# TIDA01398_MCU.net
KiCad netlist of a schematic drawn in Altium Designer
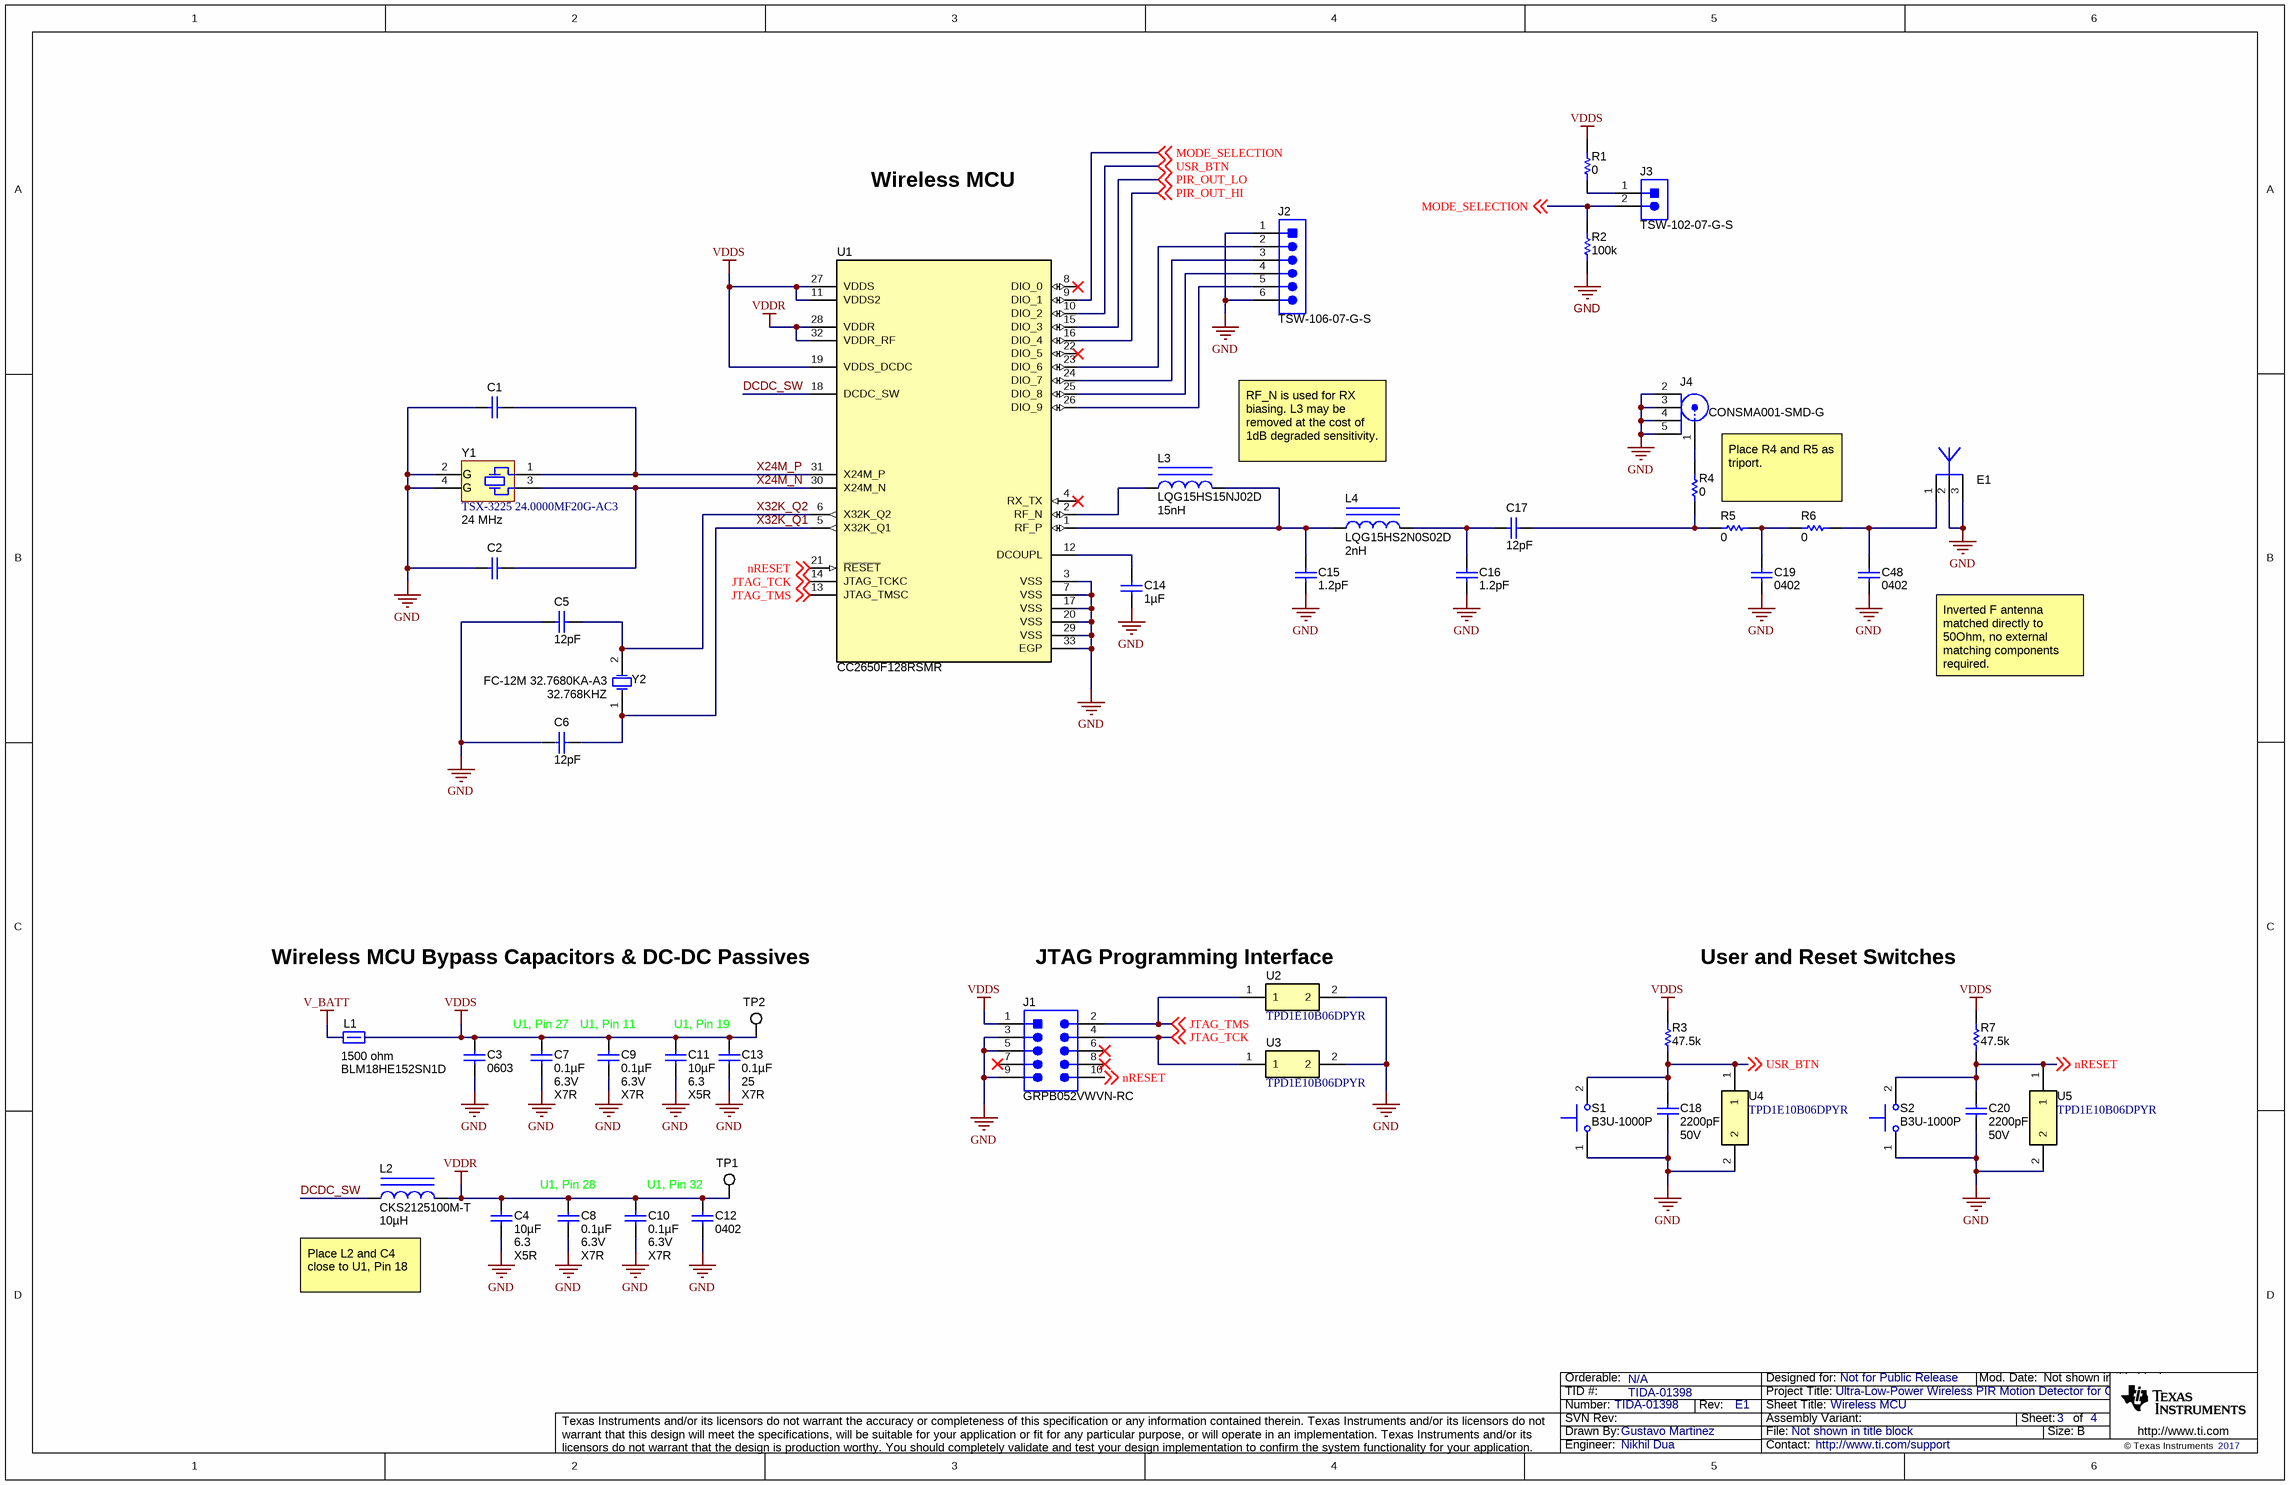
[diagram p0: TIDA01398_MCU.SchDoc]

(export (version "E")
  (design (tool "Eeschema 10.0.6"))
  (components
    (comp (ref "C1")
      (value "GRM1555C1E120JA01D")
      (footprint "0402")
      (description "CAP, CERM, 12 pF, 25 V, +/- 5%, C0G/NP0, 0402")
      (fields (field (name "MANUFACTURER") "MuRata") (field (name "PUBLISHER") "Texas Instruments"))
      (libsource (lib "Capacitor_Ceramic") (part "GRM1555C1E120JA01D"))
    )
    (comp (ref "C2")
      (value "GRM1555C1E120JA01D")
      (footprint "0402")
      (description "CAP, CERM, 12 pF, 25 V, +/- 5%, C0G/NP0, 0402")
      (fields (field (name "MANUFACTURER") "MuRata") (field (name "PUBLISHER") "Texas Instruments"))
      (libsource (lib "Capacitor_Ceramic") (part "GRM1555C1E120JA01D"))
    )
    (comp (ref "C3")
      (value "Used in BOM report")
      (footprint "0603")
      (description "CAP, CERM, xxxF, xxV, [TempCo], xx%, [PackageReference]")
      (fields (field (name "PACKAGEREFERENCE") "0603") (field (name "PUBLISHER") "Texas Instruments"))
      (libsource (lib "MiscParts") (part "Capacitor"))
    )
    (comp (ref "C4")
      (value "GRM188R60J106ME47D")
      (footprint "0603")
      (description "CAP, CERM, 10 µF, 6.3 V, +/- 20%, X5R, 0603")
      (fields
        (field (name "VALUEDISPLAYED") "10µF")
        (field (name "MANUFACTURER") "MuRata")
        (field (name "VDC_V") "6.3")
        (field (name "TEMPCO") "X5R")
        (field (name "PUBLISHER") "Texas Instruments")
      )
      (libsource (lib "Capacitor_Ceramic") (part "GRM188R60J106ME47D"))
    )
    (comp (ref "C5")
      (value "GRM1555C1E120JA01D")
      (footprint "0402")
      (description "CAP, CERM, 12 pF, 25 V, +/- 5%, C0G/NP0, 0402")
      (fields
        (field (name "VALUEDISPLAYED") "12pF")
        (field (name "MANUFACTURER") "MuRata")
        (field (name "PUBLISHER") "Texas Instruments")
      )
      (libsource (lib "Capacitor_Ceramic") (part "GRM1555C1E120JA01D"))
    )
    (comp (ref "C6")
      (value "GRM1555C1E120JA01D")
      (footprint "0402")
      (description "CAP, CERM, 12 pF, 25 V, +/- 5%, C0G/NP0, 0402")
      (fields
        (field (name "VALUEDISPLAYED") "12pF")
        (field (name "MANUFACTURER") "MuRata")
        (field (name "PUBLISHER") "Texas Instruments")
      )
      (libsource (lib "Capacitor_Ceramic") (part "GRM1555C1E120JA01D"))
    )
    (comp (ref "C7")
      (value "GRM155R70J104KA01D")
      (footprint "0402S")
      (description "CAP, CERM, 0.1 µF, 6.3 V, +/- 10%, X7R, 0402")
      (fields
        (field (name "VALUEDISPLAYED") "0.1µF")
        (field (name "MANUFACTURER") "MuRata")
        (field (name "VALUE2") "6.3V")
        (field (name "TEMPCO") "X7R")
        (field (name "PUBLISHER") "Texas Instruments")
      )
      (libsource (lib "Capacitor_Ceramic") (part "GRM155R70J104KA01D"))
    )
    (comp (ref "C8")
      (value "GRM155R70J104KA01D")
      (footprint "0402S")
      (description "CAP, CERM, 0.1 µF, 6.3 V, +/- 10%, X7R, 0402")
      (fields
        (field (name "VALUEDISPLAYED") "0.1µF")
        (field (name "MANUFACTURER") "MuRata")
        (field (name "VALUE2") "6.3V")
        (field (name "TEMPCO") "X7R")
        (field (name "PUBLISHER") "Texas Instruments")
      )
      (libsource (lib "Capacitor_Ceramic") (part "GRM155R70J104KA01D"))
    )
    (comp (ref "C9")
      (value "GRM155R70J104KA01D")
      (footprint "0402")
      (description "CAP, CERM, 0.1 µF, 6.3 V, +/- 10%, X7R, 0402")
      (fields
        (field (name "VALUEDISPLAYED") "0.1µF")
        (field (name "MANUFACTURER") "MuRata")
        (field (name "VALUE2") "6.3V")
        (field (name "TEMPCO") "X7R")
        (field (name "PUBLISHER") "Texas Instruments")
      )
      (libsource (lib "Capacitor_Ceramic") (part "GRM155R70J104KA01D"))
    )
    (comp (ref "C10")
      (value "GRM155R70J104KA01D")
      (footprint "0402S")
      (description "CAP, CERM, 0.1 µF, 6.3 V, +/- 10%, X7R, 0402")
      (fields
        (field (name "VALUEDISPLAYED") "0.1µF")
        (field (name "MANUFACTURER") "MuRata")
        (field (name "VALUE2") "6.3V")
        (field (name "TEMPCO") "X7R")
        (field (name "PUBLISHER") "Texas Instruments")
      )
      (libsource (lib "Capacitor_Ceramic") (part "GRM155R70J104KA01D"))
    )
    (comp (ref "C11")
      (value "GRM188R60J106ME47D")
      (footprint "0603")
      (description "CAP, CERM, 10 µF, 6.3 V, +/- 20%, X5R, 0603")
      (fields
        (field (name "VALUEDISPLAYED") "10µF")
        (field (name "MANUFACTURER") "MuRata")
        (field (name "VDC_V") "6.3")
        (field (name "TEMPCO") "X5R")
        (field (name "PUBLISHER") "Texas Instruments")
      )
      (libsource (lib "Capacitor_Ceramic") (part "GRM188R60J106ME47D"))
    )
    (comp (ref "C12")
      (value "Used in BOM report")
      (footprint "0402S")
      (description "CAP, CERM, xxxF, xxV, [TempCo], xx%, [PackageReference]")
      (fields (field (name "PACKAGEREFERENCE") "0402") (field (name "PUBLISHER") "Texas Instruments"))
      (libsource (lib "MiscParts") (part "Capacitor"))
    )
    (comp (ref "C13")
      (value "GRM188R71E104KA01D")
      (footprint "0603")
      (description "CAP, CERM, 0.1 µF, 25 V, +/- 10%, X7R, 0603")
      (fields
        (field (name "VALUEDISPLAYED") "0.1µF")
        (field (name "MANUFACTURER") "MuRata")
        (field (name "VDC_V") "25")
        (field (name "TEMPCO") "X7R")
        (field (name "PUBLISHER") "Texas Instruments")
      )
      (libsource (lib "Capacitor_Ceramic") (part "GRM188R71E104KA01D"))
    )
    (comp (ref "C14")
      (value "GRM155R61A105KE15D")
      (footprint "0402")
      (description "CAP, CERM, 1 µF, 10 V, +/- 10%, X5R, 0402")
      (fields
        (field (name "VALUEDISPLAYED") "1µF")
        (field (name "MANUFACTURER") "MuRata")
        (field (name "PUBLISHER") "Texas Instruments")
      )
      (libsource (lib "Capacitor_Ceramic") (part "GRM155R61A105KE15D"))
    )
    (comp (ref "C15")
      (value "GRM1555C1H1R2BA01D")
      (footprint "0402S")
      (description "CAP, CERM, 1.2 pF, 50 V, +/- 8.3%, C0G/NP0, 0402")
      (fields
        (field (name "VALUEDISPLAYED") "1.2pF")
        (field (name "MANUFACTURER") "MuRata")
        (field (name "PUBLISHER") "Texas Instruments")
      )
      (libsource (lib "Capacitor_Ceramic") (part "GRM1555C1H1R2BA01D"))
    )
    (comp (ref "C16")
      (value "GRM1555C1H1R2BA01D")
      (footprint "0402S")
      (description "CAP, CERM, 1.2 pF, 50 V, +/- 8.3%, C0G/NP0, 0402")
      (fields
        (field (name "VALUEDISPLAYED") "1.2pF")
        (field (name "MANUFACTURER") "MuRata")
        (field (name "PUBLISHER") "Texas Instruments")
      )
      (libsource (lib "Capacitor_Ceramic") (part "GRM1555C1H1R2BA01D"))
    )
    (comp (ref "C17")
      (value "GRM1555C1H120JA01D")
      (footprint "0402S")
      (description "CAP, CERM, 12 pF, 50 V, +/- 5%, C0G/NP0, 0402")
      (fields
        (field (name "VALUEDISPLAYED") "12pF")
        (field (name "MANUFACTURER") "MuRata")
        (field (name "PUBLISHER") "Texas Instruments")
      )
      (libsource (lib "Capacitor_Ceramic") (part "GRM1555C1H120JA01D"))
    )
    (comp (ref "C18")
      (value "C1005X7R1H222K")
      (footprint "0402")
      (description "CAP, CERM, 2200 pF, 50 V, +/- 10%, X7R, 0402")
      (fields
        (field (name "VALUEDISPLAYED") "2200pF")
        (field (name "MANUFACTURER") "TDK")
        (field (name "VALUE2") "50V")
        (field (name "PUBLISHER") "Texas Instruments")
      )
      (libsource (lib "Capacitor_Ceramic") (part "C1005X7R1H222K"))
    )
    (comp (ref "C19")
      (value "Used in BOM report")
      (footprint "0402S")
      (description "CAP, CERM, xxxF, xxV, [TempCo], xx%, [PackageReference]")
      (fields (field (name "PACKAGEREFERENCE") "0402") (field (name "PUBLISHER") "Texas Instruments"))
      (libsource (lib "MiscParts") (part "Capacitor"))
    )
    (comp (ref "C20")
      (value "C1005X7R1H222K")
      (footprint "0402")
      (description "CAP, CERM, 2200 pF, 50 V, +/- 10%, X7R, 0402")
      (fields
        (field (name "VALUEDISPLAYED") "2200pF")
        (field (name "MANUFACTURER") "TDK")
        (field (name "VALUE2") "50V")
        (field (name "PUBLISHER") "Texas Instruments")
      )
      (libsource (lib "Capacitor_Ceramic") (part "C1005X7R1H222K"))
    )
    (comp (ref "C48")
      (value "Used in BOM report")
      (footprint "0402S")
      (description "CAP, CERM, xxxF, xxV, [TempCo], xx%, [PackageReference]")
      (fields (field (name "PACKAGEREFERENCE") "0402") (field (name "PUBLISHER") "Texas Instruments"))
      (libsource (lib "MiscParts") (part "Capacitor"))
    )
    (comp (ref "E1")
      (value "ANTENNA_DN007A")
      (footprint "ANTENNA_DN007A")
      (description "2.4GHz PCB Antenna.  There is nothing to buy or mount.")
      (fields (field (name "SYMBOLCREATOR") "a0412235") (field (name "PUBLISHER") "Texas Instruments"))
      (libsource (lib "Other_Passive") (part "ANTENNA_DN007A"))
    )
    (comp (ref "J1")
      (value "GRPB052VWVN-RC")
      (footprint "CONN_GRPB052VWVN-RC")
      (description "Header, 50mil, 5x2, Gold, TH")
      (fields
        (field (name "MANUFACTURER") "Sullins Connector Solutions")
        (field (name "SYMBOLCREATOR") "a0412235")
        (field (name "PUBLISHER") "Texas Instruments")
      )
      (libsource (lib "Connectors_Sullins") (part "GRPB052VWVN-RC"))
    )
    (comp (ref "J2")
      (value "TSW-106-07-G-S")
      (footprint "TSW-106-07-G-S")
      (description "Header, 100mil, 6x1, Gold, TH")
      (fields
        (field (name "MANUFACTURER") "Samtec")
        (field (name "SYMBOLCREATOR") "a0412235")
        (field (name "PUBLISHER") "Texas Instruments")
      )
      (libsource (lib "Connectors_Samtec") (part "TSW-106-07-G-S"))
    )
    (comp (ref "J3")
      (value "TSW-102-07-G-S")
      (footprint "TSW-102-07-G-S")
      (description "Header, 100mil, 2x1, Gold, TH")
      (fields
        (field (name "MANUFACTURER") "Samtec")
        (field (name "SYMBOLCREATOR") "a0412235")
        (field (name "PUBLISHER") "Texas Instruments")
      )
      (libsource (lib "Connectors_Samtec") (part "TSW-102-07-G-S"))
    )
    (comp (ref "J4")
      (value "CONSMA001-SMD-G")
      (footprint "Linx_CONSMA001-SMD-G")
      (description "Jack, SMA, PCB, Gold, SMT")
      (fields
        (field (name "MANUFACTURER") "Linx Technologies")
        (field (name "SYMBOLCREATOR") "X0208326")
        (field (name "PUBLISHER") "Texas Instruments")
      )
      (libsource (lib "Connectors_Other") (part "CONSMA001-SMD-G"))
    )
    (comp (ref "L1")
      (value "1500 ohm")
      (footprint "0603")
      (description "Ferrite Bead, 1500 ohm @ 100 MHz, 0.5 A, 0603")
      (fields
        (field (name "PARTNUMBER") "BLM18HE152SN1D")
        (field (name "MANUFACTURER") "MuRata")
        (field (name "Comment") "BLM18HE152SN1D")
        (field (name "PUBLISHER") "Texas Instruments")
      )
      (libsource (lib "FerriteBead") (part "BLM18HE152SN1D"))
    )
    (comp (ref "L2")
      (value "CKS2125100M-T")
      (footprint "0805_145")
      (description "Inductor, Multilayer, Ferrite, 10uH, 0.11A, 0.52 ohm, SMD")
      (fields
        (field (name "MANUFACTURER") "Taiyo Yuden")
        (field (name "VALUEDISPLAYED") "10µH")
        (field (name "PUBLISHER") "Texas Instruments")
      )
      (libsource (lib "Inductor_Other") (part "CKS2125100M-T"))
    )
    (comp (ref "L3")
      (value "LQG15HS15NJ02D")
      (footprint "IND_LQG15H")
      (description "Inductor, Multilayer, Air Core, 15 nH, 0.3 A, 0.32 ohm, SMD")
      (fields
        (field (name "VALUEDISPLAYED") "15nH")
        (field (name "MANUFACTURER") "MuRata")
        (field (name "PUBLISHER") "Texas Instruments")
      )
      (libsource (lib "Inductor_MuRata") (part "LQG15HS15NJ02D"))
    )
    (comp (ref "L4")
      (value "LQG15HS2N0S02D")
      (footprint "IND_LQG15H")
      (description "Inductor, Multilayer, Air Core, 2 nH, 0.3 A, 0.1 ohm, SMD")
      (fields
        (field (name "VALUEDISPLAYED") "2nH")
        (field (name "MANUFACTURER") "MuRata")
        (field (name "PUBLISHER") "Texas Instruments")
      )
      (libsource (lib "Inductor_MuRata") (part "LQG15HS2N0S02D"))
    )
    (comp (ref "R1")
      (value "CRCW04020000Z0ED")
      (footprint "0402")
      (description "RES, 0, 5%, 0.063 W, 0402")
      (fields
        (field (name "VALUEDISPLAYED") "0")
        (field (name "MANUFACTURER") "Vishay-Dale")
        (field (name "PUBLISHER") "Texas Instruments")
      )
      (libsource (lib "Resistor_0402") (part "CRCW04020000Z0ED"))
    )
    (comp (ref "R2")
      (value "CRCW0402100KFKED")
      (footprint "0402")
      (description "RES, 100 k, 1%, 0.063 W, 0402")
      (fields
        (field (name "VALUEDISPLAYED") "100k")
        (field (name "MANUFACTURER") "Vishay-Dale")
        (field (name "PUBLISHER") "Texas Instruments")
      )
      (libsource (lib "Resistor_0402") (part "CRCW0402100KFKED"))
    )
    (comp (ref "R3")
      (value "CRCW040247K5FKED")
      (footprint "0402")
      (description "RES, 47.5 k, 1%, 0.063 W, 0402")
      (fields
        (field (name "VALUEDISPLAYED") "47.5k")
        (field (name "MANUFACTURER") "Vishay-Dale")
        (field (name "PUBLISHER") "Texas Instruments")
      )
      (libsource (lib "Resistor_0402") (part "CRCW040247K5FKED"))
    )
    (comp (ref "R4")
      (value "CRCW04020000Z0ED")
      (footprint "0402S")
      (description "RES, 0, 5%, 0.063 W, 0402")
      (fields
        (field (name "VALUEDISPLAYED") "0")
        (field (name "MANUFACTURER") "Vishay-Dale")
        (field (name "PUBLISHER") "Texas Instruments")
      )
      (libsource (lib "Resistor_0402") (part "CRCW04020000Z0ED"))
    )
    (comp (ref "R5")
      (value "CRCW04020000Z0ED")
      (footprint "0402S")
      (description "RES, 0, 5%, 0.063 W, 0402")
      (fields
        (field (name "VALUEDISPLAYED") "0")
        (field (name "MANUFACTURER") "Vishay-Dale")
        (field (name "PUBLISHER") "Texas Instruments")
      )
      (libsource (lib "Resistor_0402") (part "CRCW04020000Z0ED"))
    )
    (comp (ref "R6")
      (value "CRCW04020000Z0ED")
      (footprint "0402S")
      (description "RES, 0, 5%, 0.063 W, 0402")
      (fields
        (field (name "VALUEDISPLAYED") "0")
        (field (name "MANUFACTURER") "Vishay-Dale")
        (field (name "PUBLISHER") "Texas Instruments")
      )
      (libsource (lib "Resistor_0402") (part "CRCW04020000Z0ED"))
    )
    (comp (ref "R7")
      (value "CRCW040247K5FKED")
      (footprint "0402")
      (description "RES, 47.5 k, 1%, 0.063 W, 0402")
      (fields
        (field (name "VALUEDISPLAYED") "47.5k")
        (field (name "MANUFACTURER") "Vishay-Dale")
        (field (name "PUBLISHER") "Texas Instruments")
      )
      (libsource (lib "Resistor_0402") (part "CRCW040247K5FKED"))
    )
    (comp (ref "S1")
      (value "B3U-1000P")
      (footprint "SW_B3U-1000P")
      (description "SWITCH TACTILE SPST-NO 0.05A 12V")
      (fields
        (field (name "MANUFACTURER") "Omron Electronic Components")
        (field (name "SYMBOLCREATOR") "a0412235")
        (field (name "PUBLISHER") "Texas Instruments")
      )
      (libsource (lib "Switches") (part "B3U-1000P"))
    )
    (comp (ref "S2")
      (value "B3U-1000P")
      (footprint "SW_B3U-1000P")
      (description "SWITCH TACTILE SPST-NO 0.05A 12V")
      (fields
        (field (name "MANUFACTURER") "Omron Electronic Components")
        (field (name "SYMBOLCREATOR") "a0412235")
        (field (name "PUBLISHER") "Texas Instruments")
      )
      (libsource (lib "Switches") (part "B3U-1000P"))
    )
    (comp (ref "TP1")
      (value "5015")
      (footprint "Connectors_Keystone:Testpoint_Keystone_Miniature")
      (description "Test Point, Miniature, SMT")
      (fields (field (name "MANUFACTURER") "Keystone") (field (name "PUBLISHER") "Texas Instruments"))
      (libsource (lib "Connectors") (part "5015"))
    )
    (comp (ref "TP2")
      (value "5015")
      (footprint "Connectors_Keystone:Testpoint_Keystone_Miniature")
      (description "Test Point, Miniature, SMT")
      (fields (field (name "MANUFACTURER") "Keystone") (field (name "PUBLISHER") "Texas Instruments"))
      (libsource (lib "Connectors") (part "5015"))
    )
    (comp (ref "U1")
      (value "CC2650F128RSMR")
      (footprint "RSM0032B")
      (description "Ultra low-power ARM Cortex M3 2.4 GHz Radio MCU, RSM0032B")
      (fields
        (field (name "ALTERNATE PARTNUMBER") "CC2650F128RSMT")
        (field (name "MANUFACTURER") "Texas Instruments")
        (field (name "SYMBOLCREATOR") "Altium")
        (field (name "PUBLISHER") "Texas Instruments")
      )
      (libsource (lib "TI_Pre_Release") (part "CC2650F128RSMR"))
    )
    (comp (ref "U2")
      (value "TPD1E10B06DPYR")
      (footprint "DPY0002A")
      (fields
        (field (name "MANUFACTURER") "Texas Instruments")
        (field (name "ALTERNATE PARTNUMBER") "Equivalent")
      )
      (libsource (lib "TI Interface ESD EMI Protection") (part "TPD1E10B06DPYR"))
    )
    (comp (ref "U3")
      (value "TPD1E10B06DPYR")
      (footprint "DPY0002A")
      (fields
        (field (name "MANUFACTURER") "Texas Instruments")
        (field (name "ALTERNATE PARTNUMBER") "Equivalent")
      )
      (libsource (lib "TI Interface ESD EMI Protection") (part "TPD1E10B06DPYR"))
    )
    (comp (ref "U4")
      (value "TPD1E10B06DPYR")
      (footprint "DPY0002A")
      (fields
        (field (name "MANUFACTURER") "Texas Instruments")
        (field (name "ALTERNATE PARTNUMBER") "Equivalent")
      )
      (libsource (lib "") (part "TPD1E10B06DPYR_1"))
    )
    (comp (ref "U5")
      (value "TPD1E10B06DPYR")
      (footprint "DPY0002A")
      (fields
        (field (name "MANUFACTURER") "Texas Instruments")
        (field (name "ALTERNATE PARTNUMBER") "Equivalent")
      )
      (libsource (lib "") (part "TPD1E10B06DPYR_1"))
    )
    (comp (ref "Y1")
      (value "TSX-3225 24.0000MF20G-AC3")
      (footprint "EPSON_TSX-3225")
      (description "Crystal, 24 MHz, 9 pF, SMD")
      (fields
        (field (name "FREQUENCY") "24 MHz")
        (field (name "MANUFACTURER") "Epson")
        (field (name "SYMBOLCREATOR") "a0412235")
        (field (name "PUBLISHER") "Texas Instruments")
      )
      (libsource (lib "Oscillators") (part "TSX-3225 24.0000MF20G-AC3"))
    )
    (comp (ref "Y2")
      (value "FC-12M 32.7680KA-A3")
      (footprint "Epson_FC-12M")
      (description "Crystal, 32.768kHz, 12.5pF, SMD")
      (fields
        (field (name "FREQUENCY") "32.768KHZ")
        (field (name "MANUFACTURER") "Epson")
        (field (name "SYMBOLCREATOR") "a0412235")
        (field (name "PUBLISHER") "Texas Instruments")
      )
      (libsource (lib "Oscillators") (part "FC-12M 32.7680KA-A3"))
    )
  )
  (nets
    (net (code "1") (name "/DCDC_SW") (class "Default")
      (node (ref "L2") (pin "1") (pinfunction "1_1") (pintype "passive"))
      (node (ref "U1") (pin "18") (pinfunction "DCDC_SW_18") (pintype "power_in"))
    )
    (net (code "2") (name "/X24M_N") (class "Default")
      (node (ref "C2") (pin "2") (pinfunction "2_2") (pintype "passive"))
      (node (ref "U1") (pin "30") (pinfunction "X24M_N_30") (pintype "passive"))
      (node (ref "Y1") (pin "3") (pinfunction "3_3") (pintype "passive"))
    )
    (net (code "3") (name "/X24M_P") (class "Default")
      (node (ref "C1") (pin "2") (pinfunction "2_2") (pintype "passive"))
      (node (ref "U1") (pin "31") (pinfunction "X24M_P_31") (pintype "passive"))
      (node (ref "Y1") (pin "1") (pinfunction "1_1") (pintype "passive"))
    )
    (net (code "4") (name "/X32K_Q1") (class "Default")
      (node (ref "C6") (pin "1") (pinfunction "1_1") (pintype "passive"))
      (node (ref "U1") (pin "5") (pinfunction "X32K_Q1_5") (pintype "output"))
      (node (ref "Y2") (pin "1") (pinfunction "OSC1_1") (pintype "passive"))
    )
    (net (code "5") (name "/X32K_Q2") (class "Default")
      (node (ref "C5") (pin "1") (pinfunction "1_1") (pintype "passive"))
      (node (ref "U1") (pin "6") (pinfunction "X32K_Q2_6") (pintype "output"))
      (node (ref "Y2") (pin "2") (pinfunction "OSC2_2") (pintype "passive"))
    )
    (net (code "6") (name "GND") (class "Default")
      (node (ref "C1") (pin "1") (pinfunction "1_1") (pintype "passive"))
      (node (ref "C10") (pin "2") (pinfunction "2_2") (pintype "passive"))
      (node (ref "C11") (pin "1") (pinfunction "1_1") (pintype "passive"))
      (node (ref "C12") (pin "2") (pinfunction "2_2") (pintype "passive"))
      (node (ref "C13") (pin "1") (pinfunction "1_1") (pintype "passive"))
      (node (ref "C14") (pin "2") (pinfunction "2_2") (pintype "passive"))
      (node (ref "C15") (pin "2") (pinfunction "2_2") (pintype "passive"))
      (node (ref "C16") (pin "2") (pinfunction "2_2") (pintype "passive"))
      (node (ref "C18") (pin "1") (pinfunction "1_1") (pintype "passive"))
      (node (ref "C19") (pin "1") (pinfunction "1_1") (pintype "passive"))
      (node (ref "C2") (pin "1") (pinfunction "1_1") (pintype "passive"))
      (node (ref "C20") (pin "1") (pinfunction "1_1") (pintype "passive"))
      (node (ref "C3") (pin "2") (pinfunction "2_2") (pintype "passive"))
      (node (ref "C4") (pin "1") (pinfunction "1_1") (pintype "passive"))
      (node (ref "C48") (pin "1") (pinfunction "1_1") (pintype "passive"))
      (node (ref "C5") (pin "2") (pinfunction "2_2") (pintype "passive"))
      (node (ref "C6") (pin "2") (pinfunction "2_2") (pintype "passive"))
      (node (ref "C7") (pin "2") (pinfunction "2_2") (pintype "passive"))
      (node (ref "C8") (pin "2") (pinfunction "2_2") (pintype "passive"))
      (node (ref "C9") (pin "2") (pinfunction "2_2") (pintype "passive"))
      (node (ref "E1") (pin "2") (pintype "passive"))
      (node (ref "E1") (pin "3") (pintype "passive"))
      (node (ref "J1") (pin "3") (pinfunction "3_3") (pintype "passive"))
      (node (ref "J1") (pin "5") (pinfunction "5_5") (pintype "passive"))
      (node (ref "J1") (pin "9") (pinfunction "9_9") (pintype "passive"))
      (node (ref "J2") (pin "1") (pinfunction "1_1") (pintype "passive"))
      (node (ref "J2") (pin "6") (pinfunction "6_6") (pintype "passive"))
      (node (ref "J4") (pin "2") (pinfunction "2_2") (pintype "passive"))
      (node (ref "J4") (pin "3") (pinfunction "3_3") (pintype "passive"))
      (node (ref "J4") (pin "4") (pinfunction "4_4") (pintype "passive"))
      (node (ref "J4") (pin "5") (pinfunction "5_5") (pintype "passive"))
      (node (ref "R2") (pin "1") (pinfunction "1_1") (pintype "passive"))
      (node (ref "S1") (pin "1") (pinfunction "1_1") (pintype "passive"))
      (node (ref "S2") (pin "1") (pinfunction "1_1") (pintype "passive"))
      (node (ref "U1") (pin "17") (pinfunction "VSS_17") (pintype "power_in"))
      (node (ref "U1") (pin "20") (pinfunction "VSS_20") (pintype "power_in"))
      (node (ref "U1") (pin "29") (pinfunction "VSS_29") (pintype "power_in"))
      (node (ref "U1") (pin "3") (pinfunction "VSS_3") (pintype "power_in"))
      (node (ref "U1") (pin "33") (pinfunction "EGP_33") (pintype "power_in"))
      (node (ref "U1") (pin "7") (pinfunction "VSS_7") (pintype "power_in"))
      (node (ref "U2") (pin "2") (pinfunction "2_2") (pintype "passive"))
      (node (ref "U3") (pin "2") (pinfunction "2_2") (pintype "passive"))
      (node (ref "U4") (pin "2") (pinfunction "2_2") (pintype "passive"))
      (node (ref "U5") (pin "2") (pinfunction "2_2") (pintype "passive"))
      (node (ref "Y1") (pin "2") (pinfunction "GND_2") (pintype "power_in"))
      (node (ref "Y1") (pin "4") (pinfunction "GND_4") (pintype "power_in"))
    )
    (net (code "7") (name "JTAG_TCK") (class "Default")
      (node (ref "J1") (pin "4") (pinfunction "4_4") (pintype "passive"))
      (node (ref "U1") (pin "14") (pinfunction "JTAG_TCKC_14") (pintype "passive"))
      (node (ref "U3") (pin "1") (pinfunction "1_1") (pintype "passive"))
    )
    (net (code "8") (name "JTAG_TMS") (class "Default")
      (node (ref "J1") (pin "2") (pinfunction "2_2") (pintype "passive"))
      (node (ref "U1") (pin "13") (pinfunction "JTAG_TMSC_13") (pintype "passive"))
      (node (ref "U2") (pin "1") (pinfunction "1_1") (pintype "passive"))
    )
    (net (code "9") (name "MODE_SELECTION") (class "Default")
      (node (ref "J3") (pin "2") (pinfunction "2_2") (pintype "passive"))
      (node (ref "R2") (pin "2") (pinfunction "2_2") (pintype "passive"))
      (node (ref "U1") (pin "9") (pinfunction "DIO_1_9") (pintype "bidirectional"))
    )
    (net (code "10") (name "Net-(C16-Pad1)") (class "Default")
      (node (ref "C16") (pin "1") (pinfunction "1_1") (pintype "passive"))
      (node (ref "C17") (pin "2") (pinfunction "2_2") (pintype "passive"))
      (node (ref "L4") (pin "2") (pinfunction "2_2") (pintype "passive"))
    )
    (net (code "11") (name "Net-(C17-Pad1)") (class "Default")
      (node (ref "C17") (pin "1") (pinfunction "1_1") (pintype "passive"))
      (node (ref "R4") (pin "1") (pinfunction "1_1") (pintype "passive"))
      (node (ref "R5") (pin "1") (pinfunction "1_1") (pintype "passive"))
    )
    (net (code "12") (name "Net-(C19-Pad2)") (class "Default")
      (node (ref "C19") (pin "2") (pinfunction "2_2") (pintype "passive"))
      (node (ref "R5") (pin "2") (pinfunction "2_2") (pintype "passive"))
      (node (ref "R6") (pin "1") (pinfunction "1_1") (pintype "passive"))
    )
    (net (code "13") (name "Net-(C48-Pad2)") (class "Default")
      (node (ref "C48") (pin "2") (pinfunction "2_2") (pintype "passive"))
      (node (ref "E1") (pin "1") (pintype "passive"))
      (node (ref "R6") (pin "2") (pinfunction "2_2") (pintype "passive"))
    )
    (net (code "14") (name "Net-(J3-Pad1)") (class "Default")
      (node (ref "J3") (pin "1") (pinfunction "1_1") (pintype "passive"))
      (node (ref "R1") (pin "1") (pinfunction "1_1") (pintype "passive"))
    )
    (net (code "15") (name "Net-(J4-Pad1)") (class "Default")
      (node (ref "J4") (pin "1") (pinfunction "1_1") (pintype "passive"))
      (node (ref "R4") (pin "2") (pinfunction "2_2") (pintype "passive"))
    )
    (net (code "16") (name "Net-(U1-DCOUPL)") (class "Default")
      (node (ref "C14") (pin "1") (pinfunction "1_1") (pintype "passive"))
      (node (ref "U1") (pin "12") (pinfunction "DCOUPL_12") (pintype "passive"))
    )
    (net (code "17") (name "Net-(U1-DIO_6)") (class "Default")
      (node (ref "J2") (pin "2") (pinfunction "2_2") (pintype "passive"))
      (node (ref "U1") (pin "23") (pinfunction "DIO_6_23") (pintype "bidirectional"))
    )
    (net (code "18") (name "Net-(U1-DIO_7)") (class "Default")
      (node (ref "J2") (pin "3") (pinfunction "3_3") (pintype "passive"))
      (node (ref "U1") (pin "24") (pinfunction "DIO_7_24") (pintype "bidirectional"))
    )
    (net (code "19") (name "Net-(U1-DIO_8)") (class "Default")
      (node (ref "J2") (pin "4") (pinfunction "4_4") (pintype "passive"))
      (node (ref "U1") (pin "25") (pinfunction "DIO_8_25") (pintype "bidirectional"))
    )
    (net (code "20") (name "Net-(U1-DIO_9)") (class "Default")
      (node (ref "J2") (pin "5") (pinfunction "5_5") (pintype "passive"))
      (node (ref "U1") (pin "26") (pinfunction "DIO_9_26") (pintype "bidirectional"))
    )
    (net (code "21") (name "Net-(U1-RF_N)") (class "Default")
      (node (ref "L3") (pin "1") (pinfunction "1_1") (pintype "passive"))
      (node (ref "U1") (pin "2") (pinfunction "RF_N_2") (pintype "bidirectional"))
    )
    (net (code "22") (name "Net-(U1-RF_P)") (class "Default")
      (node (ref "C15") (pin "1") (pinfunction "1_1") (pintype "passive"))
      (node (ref "L3") (pin "2") (pinfunction "2_2") (pintype "passive"))
      (node (ref "L4") (pin "1") (pinfunction "1_1") (pintype "passive"))
      (node (ref "U1") (pin "1") (pinfunction "RF_P_1") (pintype "bidirectional"))
    )
    (net (code "23") (name "PIR_OUT_HI") (class "Default")
      (node (ref "U1") (pin "16") (pinfunction "DIO_4_16") (pintype "bidirectional"))
    )
    (net (code "24") (name "PIR_OUT_LO") (class "Default")
      (node (ref "U1") (pin "15") (pinfunction "DIO_3_15") (pintype "bidirectional"))
    )
    (net (code "25") (name "USR_BTN") (class "Default")
      (node (ref "C18") (pin "2") (pinfunction "2_2") (pintype "passive"))
      (node (ref "R3") (pin "1") (pinfunction "1_1") (pintype "passive"))
      (node (ref "S1") (pin "2") (pinfunction "2_2") (pintype "passive"))
      (node (ref "U1") (pin "10") (pinfunction "DIO_2_10") (pintype "bidirectional"))
      (node (ref "U4") (pin "1") (pinfunction "1_1") (pintype "passive"))
    )
    (net (code "26") (name "VDDR") (class "Default")
      (node (ref "C10") (pin "1") (pinfunction "1_1") (pintype "passive"))
      (node (ref "C12") (pin "1") (pinfunction "1_1") (pintype "passive"))
      (node (ref "C4") (pin "2") (pinfunction "2_2") (pintype "passive"))
      (node (ref "C8") (pin "1") (pinfunction "1_1") (pintype "passive"))
      (node (ref "L2") (pin "2") (pinfunction "2_2") (pintype "passive"))
      (node (ref "TP1") (pin "1") (pintype "passive"))
      (node (ref "U1") (pin "28") (pinfunction "VDDR_28") (pintype "power_in"))
      (node (ref "U1") (pin "32") (pinfunction "VDDR_RF_32") (pintype "power_in"))
    )
    (net (code "27") (name "VDDS") (class "Default")
      (node (ref "C11") (pin "2") (pinfunction "2_2") (pintype "passive"))
      (node (ref "C13") (pin "2") (pinfunction "2_2") (pintype "passive"))
      (node (ref "C3") (pin "1") (pinfunction "1_1") (pintype "passive"))
      (node (ref "C7") (pin "1") (pinfunction "1_1") (pintype "passive"))
      (node (ref "C9") (pin "1") (pinfunction "1_1") (pintype "passive"))
      (node (ref "J1") (pin "1") (pinfunction "1_1") (pintype "passive"))
      (node (ref "L1") (pin "2") (pinfunction "2_2") (pintype "passive"))
      (node (ref "R1") (pin "2") (pinfunction "2_2") (pintype "passive"))
      (node (ref "R3") (pin "2") (pinfunction "2_2") (pintype "passive"))
      (node (ref "R7") (pin "2") (pinfunction "2_2") (pintype "passive"))
      (node (ref "TP2") (pin "1") (pintype "passive"))
      (node (ref "U1") (pin "11") (pinfunction "VDDS2_11") (pintype "power_in"))
      (node (ref "U1") (pin "19") (pinfunction "VDDS_DCDC_19") (pintype "power_in"))
      (node (ref "U1") (pin "27") (pinfunction "VDDS_27") (pintype "power_in"))
    )
    (net (code "28") (name "V_BATT") (class "Default")
      (node (ref "L1") (pin "1") (pinfunction "1_1") (pintype "passive"))
    )
    (net (code "29") (name "nRESET") (class "Default")
      (node (ref "C20") (pin "2") (pinfunction "2_2") (pintype "passive"))
      (node (ref "J1") (pin "10") (pinfunction "10_10") (pintype "passive"))
      (node (ref "R7") (pin "1") (pinfunction "1_1") (pintype "passive"))
      (node (ref "S2") (pin "2") (pinfunction "2_2") (pintype "passive"))
      (node (ref "U1") (pin "21") (pinfunction "RESET_21") (pintype "input"))
      (node (ref "U5") (pin "1") (pinfunction "1_1") (pintype "passive"))
    )
    (net (code "30") (name "unconnected-(J1-Pad6)") (class "Default")
      (node (ref "J1") (pin "6") (pinfunction "6_6") (pintype "passive+no_connect"))
    )
    (net (code "31") (name "unconnected-(J1-Pad7)") (class "Default")
      (node (ref "J1") (pin "7") (pinfunction "7_7") (pintype "passive+no_connect"))
    )
    (net (code "32") (name "unconnected-(J1-Pad8)") (class "Default")
      (node (ref "J1") (pin "8") (pinfunction "8_8") (pintype "passive+no_connect"))
    )
    (net (code "33") (name "unconnected-(U1-DIO_0-Pad8)") (class "Default")
      (node (ref "U1") (pin "8") (pinfunction "DIO_0_8") (pintype "bidirectional+no_connect"))
    )
    (net (code "34") (name "unconnected-(U1-DIO_5-Pad22)") (class "Default")
      (node (ref "U1") (pin "22") (pinfunction "DIO_5_22") (pintype "bidirectional+no_connect"))
    )
    (net (code "35") (name "unconnected-(U1-RX_TX-Pad4)") (class "Default")
      (node (ref "U1") (pin "4") (pinfunction "RX_TX_4") (pintype "input+no_connect"))
    )
  )
)
